# 04_-_MICROCONTROLLER.net
KiCad netlist of a schematic drawn in Altium Designer
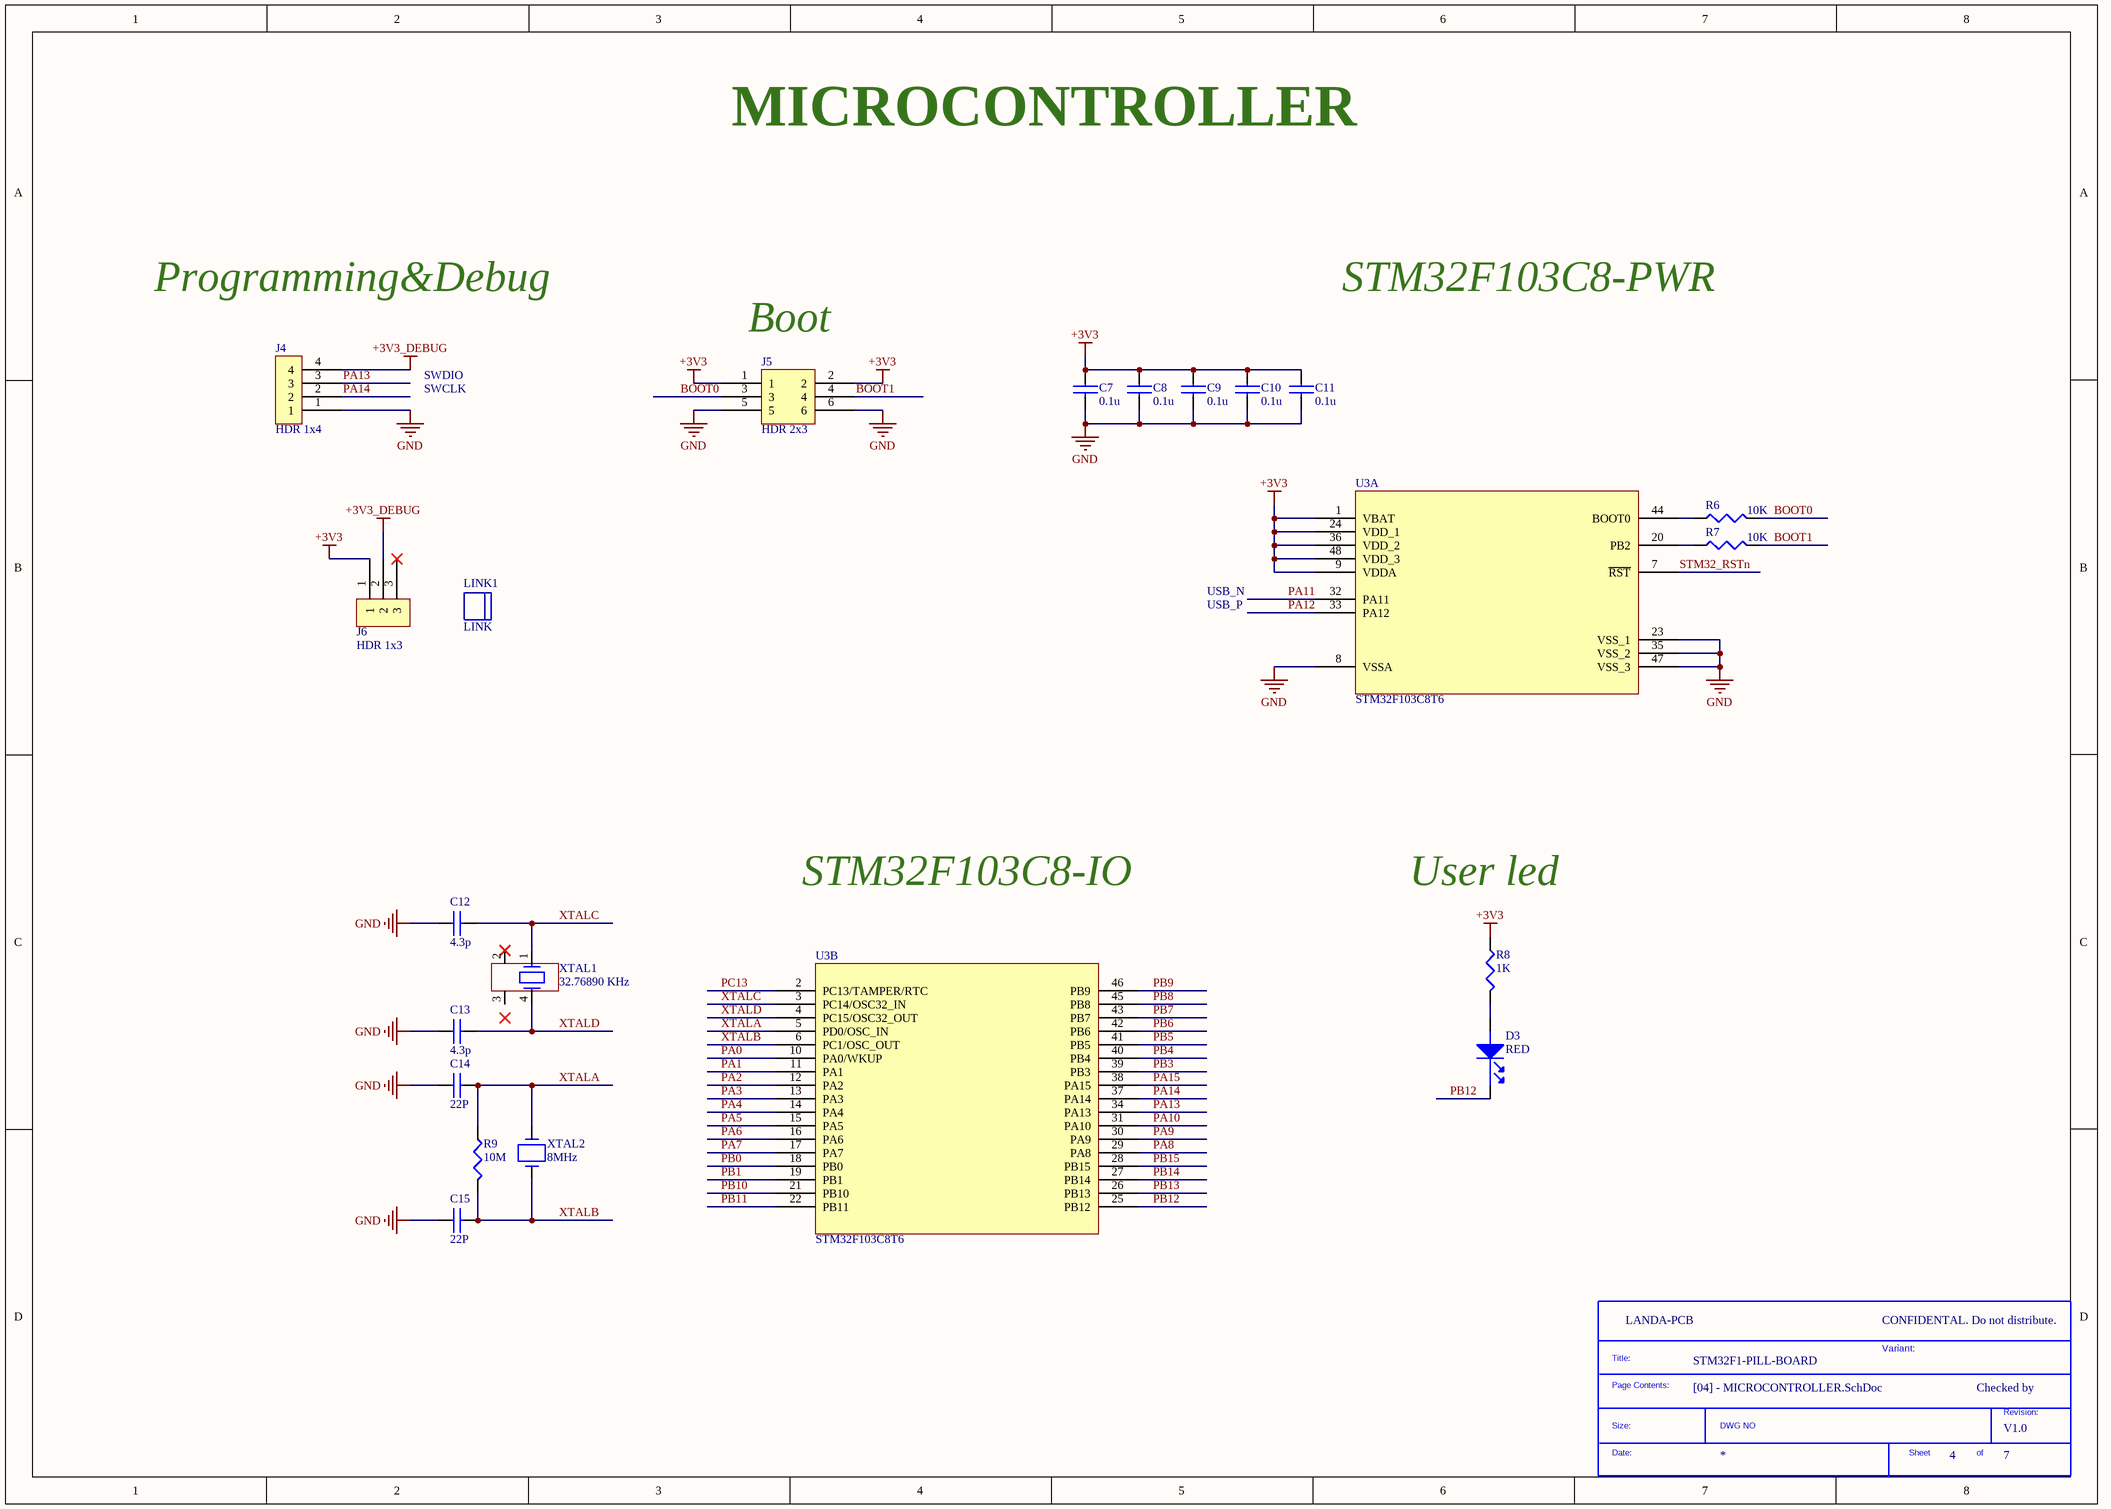
[diagram p0: [04] - MICROCONTROLLER.SchDoc]

(export (version "E")
  (design (tool "Eeschema 10.0.6"))
  (components
    (comp (ref "C7")
      (value "0.1u")
      (footprint "STM32-PILL-PCB:C0805")
      (description "CAP CER 0.1UF 50V 10% X7R 0805")
      (fields
        (field (name "MANUFACTURER") "TDK")
        (field (name "MANUFACTURER PART NUMBER") "C2012X7R1H104K085AA")
      )
      (libsource (lib "STM32-PILL-SHC") (part "C2012X7R1H104K085AA"))
    )
    (comp (ref "C8")
      (value "0.1u")
      (footprint "STM32-PILL-PCB:C0805")
      (description "CAP CER 0.1UF 50V 10% X7R 0805")
      (fields
        (field (name "MANUFACTURER") "TDK")
        (field (name "MANUFACTURER PART NUMBER") "C2012X7R1H104K085AA")
      )
      (libsource (lib "STM32-PILL-SHC") (part "C2012X7R1H104K085AA"))
    )
    (comp (ref "C9")
      (value "0.1u")
      (footprint "STM32-PILL-PCB:C0805")
      (description "CAP CER 0.1UF 50V 10% X7R 0805")
      (fields
        (field (name "MANUFACTURER") "TDK")
        (field (name "MANUFACTURER PART NUMBER") "C2012X7R1H104K085AA")
      )
      (libsource (lib "STM32-PILL-SHC") (part "C2012X7R1H104K085AA"))
    )
    (comp (ref "C10")
      (value "0.1u")
      (footprint "STM32-PILL-PCB:C0805")
      (description "CAP CER 0.1UF 50V 10% X7R 0805")
      (fields
        (field (name "MANUFACTURER") "TDK")
        (field (name "MANUFACTURER PART NUMBER") "C2012X7R1H104K085AA")
      )
      (libsource (lib "STM32-PILL-SHC") (part "C2012X7R1H104K085AA"))
    )
    (comp (ref "C11")
      (value "0.1u")
      (footprint "STM32-PILL-PCB:C0805")
      (description "CAP CER 0.1UF 50V 10% X7R 0805")
      (fields
        (field (name "MANUFACTURER") "TDK")
        (field (name "MANUFACTURER PART NUMBER") "C2012X7R1H104K085AA")
      )
      (libsource (lib "STM32-PILL-SHC") (part "C2012X7R1H104K085AA"))
    )
    (comp (ref "C12")
      (value "4.3p")
      (footprint "STM32-PILL-PCB:C0805")
      (description "CAP CER 4.3PF 50V NP0 0805")
      (fields
        (field (name "MANUFACTURER") "Kyocera AVX")
        (field (name "MANUFACTURER PART NUMBER") "08055A4R3CAT2A")
      )
      (libsource (lib "STM32-PILL-SHC") (part "08055A4R3CAT2A"))
    )
    (comp (ref "C13")
      (value "4.3p")
      (footprint "STM32-PILL-PCB:C0805")
      (description "CAP CER 4.3PF 50V NP0 0805")
      (fields
        (field (name "MANUFACTURER") "Kyocera AVX")
        (field (name "MANUFACTURER PART NUMBER") "08055A4R3CAT2A")
      )
      (libsource (lib "STM32-PILL-SHC") (part "08055A4R3CAT2A"))
    )
    (comp (ref "C14")
      (value "22P")
      (footprint "STM32-PILL-PCB:C0805")
      (description "CAP CER 22pF 50VDC C0G ±5% 0805")
      (fields
        (field (name "MANUFACTURER") "KEMET")
        (field (name "MANUFACTURER PART NUMBER") "C0805C220J5GACTU")
      )
      (libsource (lib "STM32-PILL-SHC") (part "C0805C220J5GACTU"))
    )
    (comp (ref "C15")
      (value "22P")
      (footprint "STM32-PILL-PCB:C0805")
      (description "CAP CER 22pF 50VDC C0G ±5% 0805")
      (fields
        (field (name "MANUFACTURER") "KEMET")
        (field (name "MANUFACTURER PART NUMBER") "C0805C220J5GACTU")
      )
      (libsource (lib "STM32-PILL-SHC") (part "C0805C220J5GACTU"))
    )
    (comp (ref "D3")
      (value "RED")
      (footprint "STM32-PILL-PCB:LED-0805")
      (description "LED RED 630NM 0805")
      (fields
        (field (name "MANUFACTURER") "Vishay Lite-On")
        (field (name "MANUFACTURER PART NUMBER") "LTST-C170EKT")
      )
      (libsource (lib "STM32-PILL-SHC") (part "LTST-C170EKT"))
    )
    (comp (ref "J4")
      (value "HDR 1x4")
      (footprint "STM32-PILL-PCB:HDR_1x4_2.54MM")
      (description "CONN HEADER VERT 4POS 2.54MM")
      (fields
        (field (name "MANUFACTURER") "Amphenol FCI")
        (field (name "MANUFACTURER PART NUMBER") "68001-204HLF")
      )
      (libsource (lib "STM32-PILL-SHC") (part "68001-204HLF"))
    )
    (comp (ref "J5")
      (value "HDR 2x3")
      (footprint "STM32-PILL-PCB:HDR_2X3_2.54MM")
      (description "CONN HEADER 6POS .100 STR 30AU")
      (fields
        (field (name "MANUFACTURER") "Amphenol FCI")
        (field (name "MANUFACTURER PART NUMBER") "67997-106HLF")
      )
      (libsource (lib "STM32-PILL-SHC") (part "67997-106HLF"))
    )
    (comp (ref "J6")
      (value "HDR 1x3")
      (footprint "STM32-PILL-PCB:Hdr_1x3_2.54mm")
      (description "HDR 3 POS 2.54MM STRAIGHT")
      (fields
        (field (name "MANUFACTURER") "Amphenol FCI")
        (field (name "MANUFACTURER PART NUMBER") "68000-103HLF")
      )
      (libsource (lib "STM32-PILL-SHC") (part "68000-103HLF"))
    )
    (comp (ref "LINK1")
      (value "LINK")
      (description "CONN JUMPER SHORTING .100\" GOLD")
      (fields
        (field (name "MANUFACTURER") "Sullins Connector Solutions")
        (field (name "MANUFACTURER PART NUMBER") "QPC02SXGN-RC")
      )
      (libsource (lib "STM32-PILL-SHC") (part "QPC02SXGN-RC"))
    )
    (comp (ref "R6")
      (value "10K")
      (footprint "STM32-PILL-PCB:R0805")
      (description "RES 10K OHM 1% 1/8W 0805")
      (fields
        (field (name "MANUFACTURER") "Yageo")
        (field (name "MANUFACTURER PART NUMBER") "RC0805FR-0710KL")
      )
      (libsource (lib "STM32-PILL-SHC") (part "RC0805FR-0710KL"))
    )
    (comp (ref "R7")
      (value "10K")
      (footprint "STM32-PILL-PCB:R0805")
      (description "RES 10K OHM 1% 1/8W 0805")
      (fields
        (field (name "MANUFACTURER") "Yageo")
        (field (name "MANUFACTURER PART NUMBER") "RC0805FR-0710KL")
      )
      (libsource (lib "STM32-PILL-SHC") (part "RC0805FR-0710KL"))
    )
    (comp (ref "R8")
      (value "1K")
      (footprint "STM32-PILL-PCB:R0805")
      (description "RES 1K OHM 1% 1/8W 0805")
      (fields
        (field (name "MANUFACTURER") "Yageo")
        (field (name "MANUFACTURER PART NUMBER") "RC0805FR-071KL")
      )
      (libsource (lib "STM32-PILL-SHC") (part "RC0805FR-071KL"))
    )
    (comp (ref "R9")
      (value "10M")
      (footprint "STM32-PILL-PCB:R0805")
      (description "RES 10M Ohm 1% 1/8W 0805")
      (fields (field (name "MANUFACTURER") "Rohm") (field (name "MANUFACTURER PART NUMBER") "KTR10EZPF1005"))
      (libsource (lib "STM32-PILL-SHC") (part "KTR10EZPF1005"))
    )
    (comp (ref "U3")
      (value "STM32F103C8T6")
      (footprint "STM32-PILL-PCB:LQFP-48")
      (description "STM32F103C8T6 - ARM MCU Cortex-M3, 32bit, 72 MHz")
      (fields (field (name "MANUFACTURER") "STMicroelectronics"))
      (libsource (lib "STM32-PILL-SHC") (part "STM32F103C8T6"))
    )
    (comp (ref "XTAL1")
      (value "32.76890 KHz")
      (footprint "STM32-PILL-PCB:XTAL_ABS25-32.768KHZ-6-T")
      (description "XTAL 32.7680KHZ 6PF SMD")
      (fields
        (field (name "MANUFACTURER") "Abracon")
        (field (name "MANUFACTURER PART NUMBER") "ABS25-32.768KHZ-6-T")
      )
      (libsource (lib "STM32-PILL-SHC") (part "ABS25-32.768KHZ-6-T"))
    )
    (comp (ref "XTAL2")
      (value "8MHz")
      (footprint "STM32-PILL-PCB:XTAL_11.4mmx4.9mm")
      (description "XTAL 8MHZ SMD")
      (fields
        (field (name "MANUFACTURER") "IQD")
        (field (name "MANUFACTURER PART NUMBER") "LFXTAL050985BULK")
      )
      (libsource (lib "STM32-PILL-SHC") (part "LFXTAL050985BULK"))
    )
  )
  (nets
    (net (code "1") (name "+3V3") (class "Default")
      (node (ref "C10") (pin "1") (pinfunction "1_1") (pintype "passive"))
      (node (ref "C11") (pin "1") (pinfunction "1_1") (pintype "passive"))
      (node (ref "C7") (pin "1") (pinfunction "1_1") (pintype "passive"))
      (node (ref "C8") (pin "1") (pinfunction "1_1") (pintype "passive"))
      (node (ref "C9") (pin "1") (pinfunction "1_1") (pintype "passive"))
      (node (ref "J5") (pin "1") (pinfunction "1_1") (pintype "passive"))
      (node (ref "J5") (pin "2") (pinfunction "2_2") (pintype "passive"))
      (node (ref "J6") (pin "1") (pinfunction "1_1") (pintype "passive"))
      (node (ref "R8") (pin "1") (pinfunction "1_1") (pintype "passive"))
      (node (ref "U3") (pin "1") (pinfunction "VBAT_1") (pintype "passive"))
      (node (ref "U3") (pin "24") (pinfunction "VDD_1_24") (pintype "passive"))
      (node (ref "U3") (pin "36") (pinfunction "VDD_2_36") (pintype "passive"))
      (node (ref "U3") (pin "48") (pinfunction "VDD_3_48") (pintype "passive"))
      (node (ref "U3") (pin "9") (pinfunction "VDDA_9") (pintype "passive"))
    )
    (net (code "2") (name "+3V3_DEBUG") (class "Default")
      (node (ref "J4") (pin "4") (pinfunction "4_4") (pintype "passive"))
      (node (ref "J6") (pin "2") (pinfunction "2_2") (pintype "passive"))
    )
    (net (code "4") (name "/BOOT0") (class "Default")
      (node (ref "J5") (pin "3") (pinfunction "3_3") (pintype "passive"))
      (node (ref "R6") (pin "2") (pinfunction "2_2") (pintype "passive"))
    )
    (net (code "5") (name "/BOOT1") (class "Default")
      (node (ref "J5") (pin "4") (pinfunction "4_4") (pintype "passive"))
      (node (ref "R7") (pin "2") (pinfunction "2_2") (pintype "passive"))
    )
    (net (code "6") (name "/PA0") (class "Default")
      (node (ref "U3") (pin "10") (pinfunction "PA0/WKUP_10") (pintype "passive"))
    )
    (net (code "7") (name "/PA1") (class "Default")
      (node (ref "U3") (pin "11") (pinfunction "PA1_11") (pintype "passive"))
    )
    (net (code "8") (name "/PA2") (class "Default")
      (node (ref "U3") (pin "12") (pinfunction "PA2_12") (pintype "passive"))
    )
    (net (code "9") (name "/PA3") (class "Default")
      (node (ref "U3") (pin "13") (pinfunction "PA3_13") (pintype "passive"))
    )
    (net (code "10") (name "/PA4") (class "Default")
      (node (ref "U3") (pin "14") (pinfunction "PA4_14") (pintype "passive"))
    )
    (net (code "11") (name "/PA5") (class "Default")
      (node (ref "U3") (pin "15") (pinfunction "PA5_15") (pintype "passive"))
    )
    (net (code "12") (name "/PA6") (class "Default")
      (node (ref "U3") (pin "16") (pinfunction "PA6_16") (pintype "passive"))
    )
    (net (code "13") (name "/PA7") (class "Default")
      (node (ref "U3") (pin "17") (pinfunction "PA7_17") (pintype "passive"))
    )
    (net (code "14") (name "/PA8") (class "Default")
      (node (ref "U3") (pin "29") (pinfunction "PA8_29") (pintype "passive"))
    )
    (net (code "15") (name "/PA9") (class "Default")
      (node (ref "U3") (pin "30") (pinfunction "PA9_30") (pintype "passive"))
    )
    (net (code "16") (name "/PA10") (class "Default")
      (node (ref "U3") (pin "31") (pinfunction "PA10_31") (pintype "passive"))
    )
    (net (code "17") (name "/PA11") (class "Default")
      (node (ref "U3") (pin "32") (pinfunction "PA11_32") (pintype "passive"))
    )
    (net (code "18") (name "/PA12") (class "Default")
      (node (ref "U3") (pin "33") (pinfunction "PA12_33") (pintype "passive"))
    )
    (net (code "19") (name "/PA13") (class "Default")
      (node (ref "J4") (pin "3") (pinfunction "3_3") (pintype "passive"))
      (node (ref "U3") (pin "34") (pinfunction "PA13_34") (pintype "passive"))
    )
    (net (code "20") (name "/PA14") (class "Default")
      (node (ref "J4") (pin "2") (pinfunction "2_2") (pintype "passive"))
      (node (ref "U3") (pin "37") (pinfunction "PA14_37") (pintype "passive"))
    )
    (net (code "21") (name "/PA15") (class "Default")
      (node (ref "U3") (pin "38") (pinfunction "PA15_38") (pintype "passive"))
    )
    (net (code "22") (name "/PB0") (class "Default")
      (node (ref "U3") (pin "18") (pinfunction "PB0_18") (pintype "passive"))
    )
    (net (code "23") (name "/PB1") (class "Default")
      (node (ref "U3") (pin "19") (pinfunction "PB1_19") (pintype "passive"))
    )
    (net (code "24") (name "/PB3") (class "Default")
      (node (ref "U3") (pin "39") (pinfunction "PB3_39") (pintype "passive"))
    )
    (net (code "25") (name "/PB4") (class "Default")
      (node (ref "U3") (pin "40") (pinfunction "PB4_40") (pintype "passive"))
    )
    (net (code "26") (name "/PB5") (class "Default")
      (node (ref "U3") (pin "41") (pinfunction "PB5_41") (pintype "passive"))
    )
    (net (code "27") (name "/PB6") (class "Default")
      (node (ref "U3") (pin "42") (pinfunction "PB6_42") (pintype "passive"))
    )
    (net (code "28") (name "/PB7") (class "Default")
      (node (ref "U3") (pin "43") (pinfunction "PB7_43") (pintype "passive"))
    )
    (net (code "29") (name "/PB8") (class "Default")
      (node (ref "U3") (pin "45") (pinfunction "PB8_45") (pintype "passive"))
    )
    (net (code "30") (name "/PB9") (class "Default")
      (node (ref "U3") (pin "46") (pinfunction "PB9_46") (pintype "passive"))
    )
    (net (code "31") (name "/PB10") (class "Default")
      (node (ref "U3") (pin "21") (pinfunction "PB10_21") (pintype "passive"))
    )
    (net (code "32") (name "/PB11") (class "Default")
      (node (ref "U3") (pin "22") (pinfunction "PB11_22") (pintype "passive"))
    )
    (net (code "33") (name "/PB12") (class "Default")
      (node (ref "D3") (pin "1") (pinfunction "cathode_1") (pintype "passive"))
      (node (ref "U3") (pin "25") (pinfunction "PB12_25") (pintype "passive"))
    )
    (net (code "34") (name "/PB13") (class "Default")
      (node (ref "U3") (pin "26") (pinfunction "PB13_26") (pintype "passive"))
    )
    (net (code "35") (name "/PB14") (class "Default")
      (node (ref "U3") (pin "27") (pinfunction "PB14_27") (pintype "passive"))
    )
    (net (code "36") (name "/PB15") (class "Default")
      (node (ref "U3") (pin "28") (pinfunction "PB15_28") (pintype "passive"))
    )
    (net (code "37") (name "/PC13") (class "Default")
      (node (ref "U3") (pin "2") (pinfunction "PC13/TAMPER/RTC_2") (pintype "passive"))
    )
    (net (code "38") (name "/STM32_RSTn") (class "Default")
      (node (ref "U3") (pin "7") (pinfunction "~{RST}_7") (pintype "passive"))
    )
    (net (code "39") (name "/XTALA") (class "Default")
      (node (ref "C14") (pin "2") (pinfunction "2_2") (pintype "passive"))
      (node (ref "R9") (pin "1") (pinfunction "1_1") (pintype "passive"))
      (node (ref "U3") (pin "5") (pinfunction "PD0/OSC_IN_5") (pintype "passive"))
      (node (ref "XTAL2") (pin "1") (pinfunction "1_1") (pintype "passive"))
    )
    (net (code "40") (name "/XTALB") (class "Default")
      (node (ref "C15") (pin "2") (pinfunction "2_2") (pintype "passive"))
      (node (ref "R9") (pin "2") (pinfunction "2_2") (pintype "passive"))
      (node (ref "U3") (pin "6") (pinfunction "PC1/OSC_OUT_6") (pintype "passive"))
      (node (ref "XTAL2") (pin "2") (pinfunction "2_2") (pintype "passive"))
    )
    (net (code "41") (name "/XTALC") (class "Default")
      (node (ref "C12") (pin "2") (pinfunction "2_2") (pintype "passive"))
      (node (ref "U3") (pin "3") (pinfunction "PC14/OSC32_IN_3") (pintype "passive"))
      (node (ref "XTAL1") (pin "1") (pinfunction "1_1") (pintype "passive"))
    )
    (net (code "42") (name "/XTALD") (class "Default")
      (node (ref "C13") (pin "2") (pinfunction "2_2") (pintype "passive"))
      (node (ref "U3") (pin "4") (pinfunction "PC15/OSC32_OUT_4") (pintype "passive"))
      (node (ref "XTAL1") (pin "4") (pinfunction "4_4") (pintype "passive"))
    )
    (net (code "43") (name "GND") (class "Default")
      (node (ref "C10") (pin "2") (pinfunction "2_2") (pintype "passive"))
      (node (ref "C11") (pin "2") (pinfunction "2_2") (pintype "passive"))
      (node (ref "C12") (pin "1") (pinfunction "1_1") (pintype "passive"))
      (node (ref "C13") (pin "1") (pinfunction "1_1") (pintype "passive"))
      (node (ref "C14") (pin "1") (pinfunction "1_1") (pintype "passive"))
      (node (ref "C15") (pin "1") (pinfunction "1_1") (pintype "passive"))
      (node (ref "C7") (pin "2") (pinfunction "2_2") (pintype "passive"))
      (node (ref "C8") (pin "2") (pinfunction "2_2") (pintype "passive"))
      (node (ref "C9") (pin "2") (pinfunction "2_2") (pintype "passive"))
      (node (ref "J4") (pin "1") (pinfunction "1_1") (pintype "passive"))
      (node (ref "J5") (pin "5") (pinfunction "5_5") (pintype "passive"))
      (node (ref "J5") (pin "6") (pinfunction "6_6") (pintype "passive"))
      (node (ref "U3") (pin "23") (pinfunction "VSS_1_23") (pintype "passive"))
      (node (ref "U3") (pin "35") (pinfunction "VSS_2_35") (pintype "passive"))
      (node (ref "U3") (pin "47") (pinfunction "VSS_3_47") (pintype "passive"))
      (node (ref "U3") (pin "8") (pinfunction "VSSA_8") (pintype "passive"))
    )
    (net (code "44") (name "Net-(D3-ANODE)") (class "Default")
      (node (ref "D3") (pin "2") (pinfunction "ANODE_2") (pintype "passive"))
      (node (ref "R8") (pin "2") (pinfunction "2_2") (pintype "passive"))
    )
    (net (code "45") (name "Net-(U3A-BOOT0)") (class "Default")
      (node (ref "R6") (pin "1") (pinfunction "1_1") (pintype "passive"))
      (node (ref "U3") (pin "44") (pinfunction "BOOT0_44") (pintype "passive"))
    )
    (net (code "46") (name "Net-(U3A-PB2)") (class "Default")
      (node (ref "R7") (pin "1") (pinfunction "1_1") (pintype "passive"))
      (node (ref "U3") (pin "20") (pinfunction "PB2_20") (pintype "passive"))
    )
    (net (code "47") (name "unconnected-(J6-Pad3)") (class "Default")
      (node (ref "J6") (pin "3") (pinfunction "3_3") (pintype "passive+no_connect"))
    )
    (net (code "48") (name "unconnected-(XTAL1-Pad2)") (class "Default")
      (node (ref "XTAL1") (pin "2") (pinfunction "2_2") (pintype "passive+no_connect"))
    )
    (net (code "49") (name "unconnected-(XTAL1-Pad3)") (class "Default")
      (node (ref "XTAL1") (pin "3") (pinfunction "3_3") (pintype "passive"))
    )
  )
)
